# StepperDriver_RevA.net
KiCad netlist of a schematic drawn in EAGLE
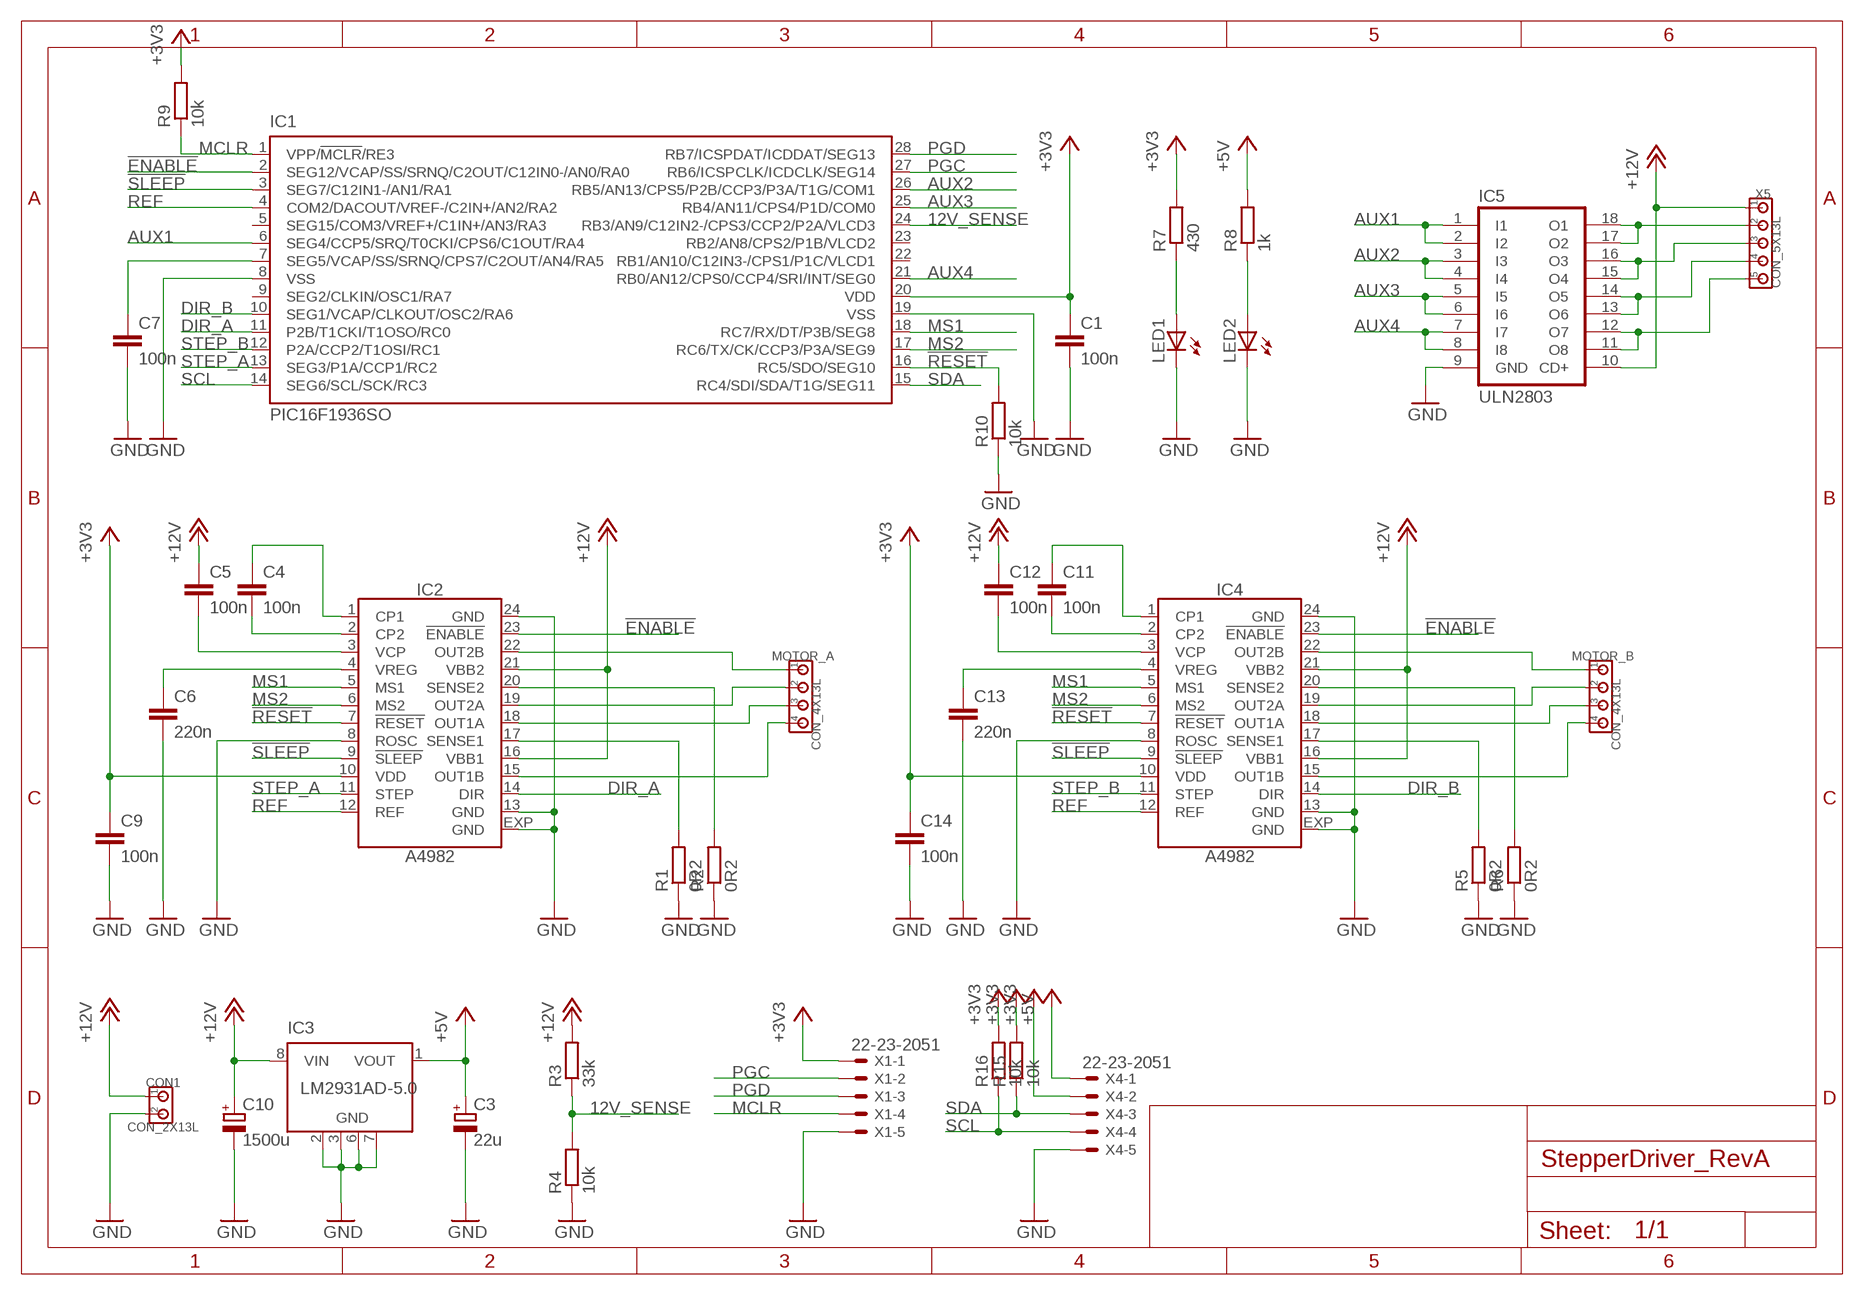
[diagram p0: schematic, sheet 1]

(export (version "E")
  (design (tool "Eeschema 10.0.6"))
  (components
    (comp (ref "C1")
      (value "100n")
      (footprint "eagle-import:C0805")
      (libsource (lib "eagle-import") (part "CC0805"))
    )
    (comp (ref "C3")
      (value "22u")
      (footprint "eagle-import:SMC_C")
      (libsource (lib "eagle-import") (part "C_POLARIZEDSMC_C"))
    )
    (comp (ref "C4")
      (value "100n")
      (footprint "eagle-import:C0805")
      (libsource (lib "eagle-import") (part "CC0805"))
    )
    (comp (ref "C5")
      (value "100n")
      (footprint "eagle-import:C0805")
      (libsource (lib "eagle-import") (part "CC0805"))
    )
    (comp (ref "C6")
      (value "220n")
      (footprint "eagle-import:C0805")
      (libsource (lib "eagle-import") (part "CC0805"))
    )
    (comp (ref "C7")
      (value "100n")
      (footprint "eagle-import:C0805")
      (libsource (lib "eagle-import") (part "CC0805"))
    )
    (comp (ref "C9")
      (value "100n")
      (footprint "eagle-import:C0805")
      (libsource (lib "eagle-import") (part "CC0805"))
    )
    (comp (ref "C10")
      (value "1500u")
      (footprint "eagle-import:10MM")
      (libsource (lib "eagle-import") (part "C_POLARIZED10MM"))
    )
    (comp (ref "C11")
      (value "100n")
      (footprint "eagle-import:C0805")
      (libsource (lib "eagle-import") (part "CC0805"))
    )
    (comp (ref "C12")
      (value "100n")
      (footprint "eagle-import:C0805")
      (libsource (lib "eagle-import") (part "CC0805"))
    )
    (comp (ref "C13")
      (value "220n")
      (footprint "eagle-import:C0805")
      (libsource (lib "eagle-import") (part "CC0805"))
    )
    (comp (ref "C14")
      (value "100n")
      (footprint "eagle-import:C0805")
      (libsource (lib "eagle-import") (part "CC0805"))
    )
    (comp (ref "CON1")
      (value "CON_2X13L")
      (footprint "eagle-import:200MIL_2X")
      (libsource (lib "eagle-import") (part "CON_2X13L"))
    )
    (comp (ref "IC1")
      (value "PIC16F1936SO")
      (footprint "eagle-import:SO28W")
      (libsource (lib "eagle-import") (part "PIC16F19SO36"))
    )
    (comp (ref "IC2")
      (value "A4982")
      (footprint "eagle-import:TSSOP-24_LP")
      (libsource (lib "eagle-import") (part "A4982"))
    )
    (comp (ref "IC3")
      (value "LM2931AD-5.0")
      (footprint "eagle-import:SO8")
      (libsource (lib "eagle-import") (part "LM2931AD-5.0"))
    )
    (comp (ref "IC4")
      (value "A4982")
      (footprint "eagle-import:TSSOP-24_LP")
      (libsource (lib "eagle-import") (part "A4982"))
    )
    (comp (ref "IC5")
      (value "ULN2803")
      (footprint "eagle-import:SO18W")
      (libsource (lib "eagle-import") (part "ULN2803"))
    )
    (comp (ref "LED1")
      (value "LED0805")
      (footprint "eagle-import:LED0805")
      (libsource (lib "eagle-import") (part "LED0805"))
    )
    (comp (ref "LED2")
      (value "LED0805")
      (footprint "eagle-import:LED0805")
      (libsource (lib "eagle-import") (part "LED0805"))
    )
    (comp (ref "MOTOR_A")
      (value "CON_4X13L")
      (footprint "eagle-import:200MIL_4X")
      (libsource (lib "eagle-import") (part "CON_4X13L"))
    )
    (comp (ref "MOTOR_B")
      (value "CON_4X13L")
      (footprint "eagle-import:200MIL_4X")
      (libsource (lib "eagle-import") (part "CON_4X13L"))
    )
    (comp (ref "R1")
      (value "0R2")
      (footprint "eagle-import:0612")
      (libsource (lib "eagle-import") (part "RESISTOR0612"))
    )
    (comp (ref "R2")
      (value "0R2")
      (footprint "eagle-import:0612")
      (libsource (lib "eagle-import") (part "RESISTOR0612"))
    )
    (comp (ref "R3")
      (value "33k")
      (footprint "eagle-import:R0805")
      (libsource (lib "eagle-import") (part "RESISTORR0805"))
    )
    (comp (ref "R4")
      (value "10k")
      (footprint "eagle-import:R0805")
      (libsource (lib "eagle-import") (part "RESISTORR0805"))
    )
    (comp (ref "R5")
      (value "0R2")
      (footprint "eagle-import:0612")
      (libsource (lib "eagle-import") (part "RESISTOR0612"))
    )
    (comp (ref "R6")
      (value "0R2")
      (footprint "eagle-import:0612")
      (libsource (lib "eagle-import") (part "RESISTOR0612"))
    )
    (comp (ref "R7")
      (value "430")
      (footprint "eagle-import:R0805")
      (libsource (lib "eagle-import") (part "RESISTORR0805"))
    )
    (comp (ref "R8")
      (value "1k")
      (footprint "eagle-import:R0805")
      (libsource (lib "eagle-import") (part "RESISTORR0805"))
    )
    (comp (ref "R9")
      (value "10k")
      (footprint "eagle-import:R0805")
      (libsource (lib "eagle-import") (part "RESISTORR0805"))
    )
    (comp (ref "R10")
      (value "10k")
      (footprint "eagle-import:R0805")
      (libsource (lib "eagle-import") (part "RESISTORR0805"))
    )
    (comp (ref "R15")
      (value "10k")
      (footprint "eagle-import:R0805")
      (libsource (lib "eagle-import") (part "RESISTORR0805"))
    )
    (comp (ref "R16")
      (value "10k")
      (footprint "eagle-import:R0805")
      (libsource (lib "eagle-import") (part "RESISTORR0805"))
    )
    (comp (ref "X1")
      (value "22-23-2051")
      (footprint "eagle-import:22-23-2051")
      (fields (field (name "MF") "MOLEX"))
      (libsource (lib "eagle-import") (part "22-23-2051"))
    )
    (comp (ref "X4")
      (value "22-23-2051")
      (footprint "eagle-import:22-23-2051")
      (fields (field (name "MF") "MOLEX"))
      (libsource (lib "eagle-import") (part "22-23-2051"))
    )
    (comp (ref "X5")
      (value "CON_5X13L")
      (footprint "eagle-import:200MIL_5X")
      (libsource (lib "eagle-import") (part "CON_5X13L"))
    )
  )
  (nets
    (net (code "1") (name "+3V3") (class "Default")
      (node (ref "C1") (pin "1") (pinfunction "1_1") (pintype "passive"))
      (node (ref "C14") (pin "1") (pinfunction "1_1") (pintype "passive"))
      (node (ref "C9") (pin "1") (pinfunction "1_1") (pintype "passive"))
      (node (ref "IC1") (pin "20") (pinfunction "VDD_20") (pintype "power_in"))
      (node (ref "IC2") (pin "10") (pinfunction "VDD_10") (pintype "bidirectional"))
      (node (ref "IC4") (pin "10") (pinfunction "VDD_10") (pintype "bidirectional"))
      (node (ref "R15") (pin "2") (pinfunction "2_2") (pintype "passive"))
      (node (ref "R16") (pin "2") (pinfunction "2_2") (pintype "passive"))
      (node (ref "R7") (pin "2") (pinfunction "2_2") (pintype "passive"))
      (node (ref "R9") (pin "2") (pinfunction "2_2") (pintype "passive"))
      (node (ref "X1") (pin "1") (pinfunction "S_1") (pintype "passive"))
      (node (ref "X4") (pin "2") (pinfunction "S_2") (pintype "passive"))
    )
    (net (code "2") (name "+5V") (class "Default")
      (node (ref "C3") (pin "+") (pinfunction "+_+") (pintype "passive"))
      (node (ref "IC3") (pin "1") (pinfunction "VOUT_1") (pintype "output"))
      (node (ref "R8") (pin "2") (pinfunction "2_2") (pintype "passive"))
      (node (ref "X4") (pin "1") (pinfunction "S_1") (pintype "passive"))
    )
    (net (code "3") (name "+12V") (class "Default")
      (node (ref "C10") (pin "+") (pinfunction "+_+") (pintype "passive"))
      (node (ref "C12") (pin "1") (pinfunction "1_1") (pintype "passive"))
      (node (ref "C5") (pin "1") (pinfunction "1_1") (pintype "passive"))
      (node (ref "CON1") (pin "1") (pinfunction "1_1") (pintype "passive"))
      (node (ref "IC2") (pin "16") (pinfunction "VBB1_16") (pintype "power_in"))
      (node (ref "IC2") (pin "21") (pinfunction "VBB2_21") (pintype "power_in"))
      (node (ref "IC3") (pin "8") (pinfunction "VIN_8") (pintype "passive"))
      (node (ref "IC4") (pin "16") (pinfunction "VBB1_16") (pintype "power_in"))
      (node (ref "IC4") (pin "21") (pinfunction "VBB2_21") (pintype "power_in"))
      (node (ref "IC5") (pin "10") (pinfunction "CD+_10") (pintype "passive"))
      (node (ref "R3") (pin "2") (pinfunction "2_2") (pintype "passive"))
      (node (ref "X5") (pin "1") (pinfunction "1_1") (pintype "passive"))
    )
    (net (code "4") (name "/12V_SENSE") (class "Default")
      (node (ref "IC1") (pin "24") (pinfunction "RB3/AN9/C12IN2-/CPS3/CCP2/P2A/VLCD3_24") (pintype "bidirectional"))
      (node (ref "R3") (pin "1") (pinfunction "1_1") (pintype "passive"))
      (node (ref "R4") (pin "2") (pinfunction "2_2") (pintype "passive"))
    )
    (net (code "5") (name "/AUX1") (class "Default")
      (node (ref "IC1") (pin "6") (pinfunction "SEG4/CCP5/SRQ/T0CKI/CPS6/C1OUT/RA4_6") (pintype "bidirectional"))
      (node (ref "IC5") (pin "1") (pinfunction "I1_1") (pintype "input"))
      (node (ref "IC5") (pin "2") (pinfunction "I2_2") (pintype "input"))
    )
    (net (code "6") (name "/AUX2") (class "Default")
      (node (ref "IC1") (pin "26") (pinfunction "RB5/AN13/CPS5/P2B/CCP3/P3A/T1G/COM1_26") (pintype "bidirectional"))
      (node (ref "IC5") (pin "3") (pinfunction "I3_3") (pintype "input"))
      (node (ref "IC5") (pin "4") (pinfunction "I4_4") (pintype "input"))
    )
    (net (code "7") (name "/AUX3") (class "Default")
      (node (ref "IC1") (pin "25") (pinfunction "RB4/AN11/CPS4/P1D/COM0_25") (pintype "bidirectional"))
      (node (ref "IC5") (pin "5") (pinfunction "I5_5") (pintype "input"))
      (node (ref "IC5") (pin "6") (pinfunction "I6_6") (pintype "input"))
    )
    (net (code "8") (name "/AUX4") (class "Default")
      (node (ref "IC1") (pin "21") (pinfunction "RB0/AN12/CPS0/CCP4/SRI/INT/SEG0_21") (pintype "bidirectional"))
      (node (ref "IC5") (pin "7") (pinfunction "I7_7") (pintype "input"))
      (node (ref "IC5") (pin "8") (pinfunction "I8_8") (pintype "input"))
    )
    (net (code "9") (name "/DIR_A") (class "Default")
      (node (ref "IC1") (pin "11") (pinfunction "P2B/T1CKI/T1OSO/RC0_11") (pintype "bidirectional"))
      (node (ref "IC2") (pin "14") (pinfunction "DIR_14") (pintype "bidirectional"))
    )
    (net (code "10") (name "/DIR_B") (class "Default")
      (node (ref "IC1") (pin "10") (pinfunction "SEG1/VCAP/CLKOUT/OSC2/RA6_10") (pintype "bidirectional"))
      (node (ref "IC4") (pin "14") (pinfunction "DIR_14") (pintype "bidirectional"))
    )
    (net (code "11") (name "/MCLR") (class "Default")
      (node (ref "IC1") (pin "1") (pinfunction "VPP/~{MCLR}/RE3_1") (pintype "input"))
      (node (ref "R9") (pin "1") (pinfunction "1_1") (pintype "passive"))
      (node (ref "X1") (pin "4") (pinfunction "S_4") (pintype "passive"))
    )
    (net (code "12") (name "/MS1") (class "Default")
      (node (ref "IC1") (pin "18") (pinfunction "RC7/RX/DT/P3B/SEG8_18") (pintype "bidirectional"))
      (node (ref "IC2") (pin "5") (pinfunction "MS1_5") (pintype "input"))
      (node (ref "IC4") (pin "5") (pinfunction "MS1_5") (pintype "input"))
    )
    (net (code "13") (name "/MS2") (class "Default")
      (node (ref "IC1") (pin "17") (pinfunction "RC6/TX/CK/CCP3/P3A/SEG9_17") (pintype "bidirectional"))
      (node (ref "IC2") (pin "6") (pinfunction "MS2_6") (pintype "input"))
      (node (ref "IC4") (pin "6") (pinfunction "MS2_6") (pintype "input"))
    )
    (net (code "14") (name "/PGC") (class "Default")
      (node (ref "IC1") (pin "27") (pinfunction "RB6/ICSPCLK/ICDCLK/SEG14_27") (pintype "bidirectional"))
      (node (ref "X1") (pin "2") (pinfunction "S_2") (pintype "passive"))
    )
    (net (code "15") (name "/PGD") (class "Default")
      (node (ref "IC1") (pin "28") (pinfunction "RB7/ICSPDAT/ICDDAT/SEG13_28") (pintype "bidirectional"))
      (node (ref "X1") (pin "3") (pinfunction "S_3") (pintype "passive"))
    )
    (net (code "16") (name "/REF") (class "Default")
      (node (ref "IC1") (pin "4") (pinfunction "COM2/DACOUT/VREF-/C2IN+/AN2/RA2_4") (pintype "bidirectional"))
      (node (ref "IC2") (pin "12") (pinfunction "REF_12") (pintype "bidirectional"))
      (node (ref "IC4") (pin "12") (pinfunction "REF_12") (pintype "bidirectional"))
    )
    (net (code "17") (name "/SCL") (class "Default")
      (node (ref "IC1") (pin "14") (pinfunction "SEG6/SCL/SCK/RC3_14") (pintype "bidirectional"))
      (node (ref "R16") (pin "1") (pinfunction "1_1") (pintype "passive"))
      (node (ref "X4") (pin "4") (pinfunction "S_4") (pintype "passive"))
    )
    (net (code "18") (name "/SDA") (class "Default")
      (node (ref "IC1") (pin "15") (pinfunction "RC4/SDI/SDA/T1G/SEG11_15") (pintype "bidirectional"))
      (node (ref "R15") (pin "1") (pinfunction "1_1") (pintype "passive"))
      (node (ref "X4") (pin "3") (pinfunction "S_3") (pintype "passive"))
    )
    (net (code "19") (name "/STEP_A") (class "Default")
      (node (ref "IC1") (pin "13") (pinfunction "SEG3/P1A/CCP1/RC2_13") (pintype "bidirectional"))
      (node (ref "IC2") (pin "11") (pinfunction "STEP_11") (pintype "bidirectional"))
    )
    (net (code "20") (name "/STEP_B") (class "Default")
      (node (ref "IC1") (pin "12") (pinfunction "P2A/CCP2/T1OSI/RC1_12") (pintype "bidirectional"))
      (node (ref "IC4") (pin "11") (pinfunction "STEP_11") (pintype "bidirectional"))
    )
    (net (code "21") (name "/~{ENABLE}") (class "Default")
      (node (ref "IC1") (pin "2") (pinfunction "SEG12/VCAP/SS/SRNQ/C2OUT/C12IN0-/AN0/RA0_2") (pintype "bidirectional"))
      (node (ref "IC2") (pin "23") (pinfunction "~{ENABLE}_23") (pintype "power_in"))
      (node (ref "IC4") (pin "23") (pinfunction "~{ENABLE}_23") (pintype "power_in"))
    )
    (net (code "22") (name "/~{RESET}") (class "Default")
      (node (ref "IC1") (pin "16") (pinfunction "RC5/SDO/SEG10_16") (pintype "bidirectional"))
      (node (ref "IC2") (pin "7") (pinfunction "~{RESET}_7") (pintype "bidirectional"))
      (node (ref "IC4") (pin "7") (pinfunction "~{RESET}_7") (pintype "bidirectional"))
      (node (ref "R10") (pin "2") (pinfunction "2_2") (pintype "passive"))
    )
    (net (code "23") (name "/~{SLEEP}") (class "Default")
      (node (ref "IC1") (pin "3") (pinfunction "SEG7/C12IN1-/AN1/RA1_3") (pintype "bidirectional"))
      (node (ref "IC2") (pin "9") (pinfunction "~{SLEEP}_9") (pintype "bidirectional"))
      (node (ref "IC4") (pin "9") (pinfunction "~{SLEEP}_9") (pintype "bidirectional"))
    )
    (net (code "24") (name "GND") (class "Default")
      (node (ref "C1") (pin "2") (pinfunction "2_2") (pintype "passive"))
      (node (ref "C10") (pin "-") (pinfunction "-_-") (pintype "passive"))
      (node (ref "C13") (pin "2") (pinfunction "2_2") (pintype "passive"))
      (node (ref "C14") (pin "2") (pinfunction "2_2") (pintype "passive"))
      (node (ref "C3") (pin "-") (pinfunction "-_-") (pintype "passive"))
      (node (ref "C6") (pin "2") (pinfunction "2_2") (pintype "passive"))
      (node (ref "C7") (pin "2") (pinfunction "2_2") (pintype "passive"))
      (node (ref "C9") (pin "2") (pinfunction "2_2") (pintype "passive"))
      (node (ref "CON1") (pin "2") (pinfunction "2_2") (pintype "passive"))
      (node (ref "IC1") (pin "19") (pinfunction "VSS_19") (pintype "power_in"))
      (node (ref "IC1") (pin "8") (pinfunction "VSS_8") (pintype "power_in"))
      (node (ref "IC2") (pin "13") (pinfunction "GND_13") (pintype "bidirectional"))
      (node (ref "IC2") (pin "24") (pinfunction "GND_24") (pintype "power_in"))
      (node (ref "IC2") (pin "8") (pinfunction "ROSC_8") (pintype "output"))
      (node (ref "IC2") (pin "EXP") (pinfunction "GND_EXP") (pintype "power_in"))
      (node (ref "IC3") (pin "2") (pinfunction "GND_2") (pintype "power_in"))
      (node (ref "IC3") (pin "3") (pinfunction "GND_3") (pintype "power_in"))
      (node (ref "IC3") (pin "6") (pinfunction "GND_6") (pintype "power_in"))
      (node (ref "IC3") (pin "7") (pinfunction "GND_7") (pintype "power_in"))
      (node (ref "IC4") (pin "13") (pinfunction "GND_13") (pintype "bidirectional"))
      (node (ref "IC4") (pin "24") (pinfunction "GND_24") (pintype "power_in"))
      (node (ref "IC4") (pin "8") (pinfunction "ROSC_8") (pintype "output"))
      (node (ref "IC4") (pin "EXP") (pinfunction "GND_EXP") (pintype "power_in"))
      (node (ref "IC5") (pin "9") (pinfunction "GND_9") (pintype "power_in"))
      (node (ref "LED1") (pin "C") (pinfunction "C_C") (pintype "passive"))
      (node (ref "LED2") (pin "C") (pinfunction "C_C") (pintype "passive"))
      (node (ref "R1") (pin "1") (pinfunction "1_1") (pintype "passive"))
      (node (ref "R10") (pin "1") (pinfunction "1_1") (pintype "passive"))
      (node (ref "R2") (pin "1") (pinfunction "1_1") (pintype "passive"))
      (node (ref "R4") (pin "1") (pinfunction "1_1") (pintype "passive"))
      (node (ref "R5") (pin "1") (pinfunction "1_1") (pintype "passive"))
      (node (ref "R6") (pin "1") (pinfunction "1_1") (pintype "passive"))
      (node (ref "X1") (pin "5") (pinfunction "S_5") (pintype "passive"))
      (node (ref "X4") (pin "5") (pinfunction "S_5") (pintype "passive"))
    )
    (net (code "25") (name "Net-(IC1-SEG5{slash}VCAP{slash}SS{slash}SRNQ{slash}CPS7{slash}C2OUT{slash}AN4{slash}RA5)") (class "Default")
      (node (ref "C7") (pin "1") (pinfunction "1_1") (pintype "passive"))
      (node (ref "IC1") (pin "7") (pinfunction "SEG5/VCAP/SS/SRNQ/CPS7/C2OUT/AN4/RA5_7") (pintype "bidirectional"))
    )
    (net (code "26") (name "Net-(IC2-CP1)") (class "Default")
      (node (ref "C4") (pin "1") (pinfunction "1_1") (pintype "passive"))
      (node (ref "IC2") (pin "1") (pinfunction "CP1_1") (pintype "input"))
    )
    (net (code "27") (name "Net-(IC2-CP2)") (class "Default")
      (node (ref "C4") (pin "2") (pinfunction "2_2") (pintype "passive"))
      (node (ref "IC2") (pin "2") (pinfunction "CP2_2") (pintype "input"))
    )
    (net (code "28") (name "Net-(IC2-OUT1A)") (class "Default")
      (node (ref "IC2") (pin "18") (pinfunction "OUT1A_18") (pintype "power_in"))
      (node (ref "MOTOR_A") (pin "3") (pinfunction "3_3") (pintype "passive"))
    )
    (net (code "29") (name "Net-(IC2-OUT1B)") (class "Default")
      (node (ref "IC2") (pin "15") (pinfunction "OUT1B_15") (pintype "bidirectional"))
      (node (ref "MOTOR_A") (pin "4") (pinfunction "4_4") (pintype "passive"))
    )
    (net (code "30") (name "Net-(IC2-OUT2A)") (class "Default")
      (node (ref "IC2") (pin "19") (pinfunction "OUT2A_19") (pintype "power_in"))
      (node (ref "MOTOR_A") (pin "2") (pinfunction "2_2") (pintype "passive"))
    )
    (net (code "31") (name "Net-(IC2-OUT2B)") (class "Default")
      (node (ref "IC2") (pin "22") (pinfunction "OUT2B_22") (pintype "power_in"))
      (node (ref "MOTOR_A") (pin "1") (pinfunction "1_1") (pintype "passive"))
    )
    (net (code "32") (name "Net-(IC2-SENSE1)") (class "Default")
      (node (ref "IC2") (pin "17") (pinfunction "SENSE1_17") (pintype "power_in"))
      (node (ref "R1") (pin "2") (pinfunction "2_2") (pintype "passive"))
    )
    (net (code "33") (name "Net-(IC2-SENSE2)") (class "Default")
      (node (ref "IC2") (pin "20") (pinfunction "SENSE2_20") (pintype "power_in"))
      (node (ref "R2") (pin "2") (pinfunction "2_2") (pintype "passive"))
    )
    (net (code "34") (name "Net-(IC2-VCP)") (class "Default")
      (node (ref "C5") (pin "2") (pinfunction "2_2") (pintype "passive"))
      (node (ref "IC2") (pin "3") (pinfunction "VCP_3") (pintype "input"))
    )
    (net (code "35") (name "Net-(IC2-VREG)") (class "Default")
      (node (ref "C6") (pin "1") (pinfunction "1_1") (pintype "passive"))
      (node (ref "IC2") (pin "4") (pinfunction "VREG_4") (pintype "input"))
    )
    (net (code "36") (name "Net-(IC4-CP1)") (class "Default")
      (node (ref "C11") (pin "1") (pinfunction "1_1") (pintype "passive"))
      (node (ref "IC4") (pin "1") (pinfunction "CP1_1") (pintype "input"))
    )
    (net (code "37") (name "Net-(IC4-CP2)") (class "Default")
      (node (ref "C11") (pin "2") (pinfunction "2_2") (pintype "passive"))
      (node (ref "IC4") (pin "2") (pinfunction "CP2_2") (pintype "input"))
    )
    (net (code "38") (name "Net-(IC4-OUT1A)") (class "Default")
      (node (ref "IC4") (pin "18") (pinfunction "OUT1A_18") (pintype "power_in"))
      (node (ref "MOTOR_B") (pin "3") (pinfunction "3_3") (pintype "passive"))
    )
    (net (code "39") (name "Net-(IC4-OUT1B)") (class "Default")
      (node (ref "IC4") (pin "15") (pinfunction "OUT1B_15") (pintype "bidirectional"))
      (node (ref "MOTOR_B") (pin "4") (pinfunction "4_4") (pintype "passive"))
    )
    (net (code "40") (name "Net-(IC4-OUT2A)") (class "Default")
      (node (ref "IC4") (pin "19") (pinfunction "OUT2A_19") (pintype "power_in"))
      (node (ref "MOTOR_B") (pin "2") (pinfunction "2_2") (pintype "passive"))
    )
    (net (code "41") (name "Net-(IC4-OUT2B)") (class "Default")
      (node (ref "IC4") (pin "22") (pinfunction "OUT2B_22") (pintype "power_in"))
      (node (ref "MOTOR_B") (pin "1") (pinfunction "1_1") (pintype "passive"))
    )
    (net (code "42") (name "Net-(IC4-SENSE1)") (class "Default")
      (node (ref "IC4") (pin "17") (pinfunction "SENSE1_17") (pintype "power_in"))
      (node (ref "R5") (pin "2") (pinfunction "2_2") (pintype "passive"))
    )
    (net (code "43") (name "Net-(IC4-SENSE2)") (class "Default")
      (node (ref "IC4") (pin "20") (pinfunction "SENSE2_20") (pintype "power_in"))
      (node (ref "R6") (pin "2") (pinfunction "2_2") (pintype "passive"))
    )
    (net (code "44") (name "Net-(IC4-VCP)") (class "Default")
      (node (ref "C12") (pin "2") (pinfunction "2_2") (pintype "passive"))
      (node (ref "IC4") (pin "3") (pinfunction "VCP_3") (pintype "input"))
    )
    (net (code "45") (name "Net-(IC4-VREG)") (class "Default")
      (node (ref "C13") (pin "1") (pinfunction "1_1") (pintype "passive"))
      (node (ref "IC4") (pin "4") (pinfunction "VREG_4") (pintype "input"))
    )
    (net (code "46") (name "Net-(IC5-O1)") (class "Default")
      (node (ref "IC5") (pin "17") (pinfunction "O2_17") (pintype "open_collector"))
      (node (ref "IC5") (pin "18") (pinfunction "O1_18") (pintype "open_collector"))
      (node (ref "X5") (pin "2") (pinfunction "2_2") (pintype "passive"))
    )
    (net (code "47") (name "Net-(IC5-O3)") (class "Default")
      (node (ref "IC5") (pin "15") (pinfunction "O4_15") (pintype "open_collector"))
      (node (ref "IC5") (pin "16") (pinfunction "O3_16") (pintype "open_collector"))
      (node (ref "X5") (pin "3") (pinfunction "3_3") (pintype "passive"))
    )
    (net (code "48") (name "Net-(IC5-O5)") (class "Default")
      (node (ref "IC5") (pin "13") (pinfunction "O6_13") (pintype "open_collector"))
      (node (ref "IC5") (pin "14") (pinfunction "O5_14") (pintype "open_collector"))
      (node (ref "X5") (pin "4") (pinfunction "4_4") (pintype "passive"))
    )
    (net (code "49") (name "Net-(IC5-O7)") (class "Default")
      (node (ref "IC5") (pin "11") (pinfunction "O8_11") (pintype "open_collector"))
      (node (ref "IC5") (pin "12") (pinfunction "O7_12") (pintype "open_collector"))
      (node (ref "X5") (pin "5") (pinfunction "5_5") (pintype "passive"))
    )
    (net (code "50") (name "Net-(LED1-PadA)") (class "Default")
      (node (ref "LED1") (pin "A") (pinfunction "A_A") (pintype "passive"))
      (node (ref "R7") (pin "1") (pinfunction "1_1") (pintype "passive"))
    )
    (net (code "51") (name "Net-(LED2-PadA)") (class "Default")
      (node (ref "LED2") (pin "A") (pinfunction "A_A") (pintype "passive"))
      (node (ref "R8") (pin "1") (pinfunction "1_1") (pintype "passive"))
    )
    (net (code "52") (name "unconnected-(IC1-RB1{slash}AN10{slash}C12IN3-{slash}CPS1{slash}P1C{slash}VLCD1-Pad22)") (class "Default")
      (node (ref "IC1") (pin "22") (pinfunction "RB1/AN10/C12IN3-/CPS1/P1C/VLCD1_22") (pintype "bidirectional"))
    )
    (net (code "53") (name "unconnected-(IC1-RB2{slash}AN8{slash}CPS2{slash}P1B{slash}VLCD2-Pad23)") (class "Default")
      (node (ref "IC1") (pin "23") (pinfunction "RB2/AN8/CPS2/P1B/VLCD2_23") (pintype "bidirectional"))
    )
    (net (code "54") (name "unconnected-(IC1-SEG2{slash}CLKIN{slash}OSC1{slash}RA7-Pad9)") (class "Default")
      (node (ref "IC1") (pin "9") (pinfunction "SEG2/CLKIN/OSC1/RA7_9") (pintype "bidirectional"))
    )
    (net (code "55") (name "unconnected-(IC1-SEG15{slash}COM3{slash}VREF+{slash}C1IN+{slash}AN3{slash}RA3-Pad5)") (class "Default")
      (node (ref "IC1") (pin "5") (pinfunction "SEG15/COM3/VREF+/C1IN+/AN3/RA3_5") (pintype "bidirectional"))
    )
  )
)
